# Sensors.net
KiCad netlist of a schematic drawn in Altium Designer
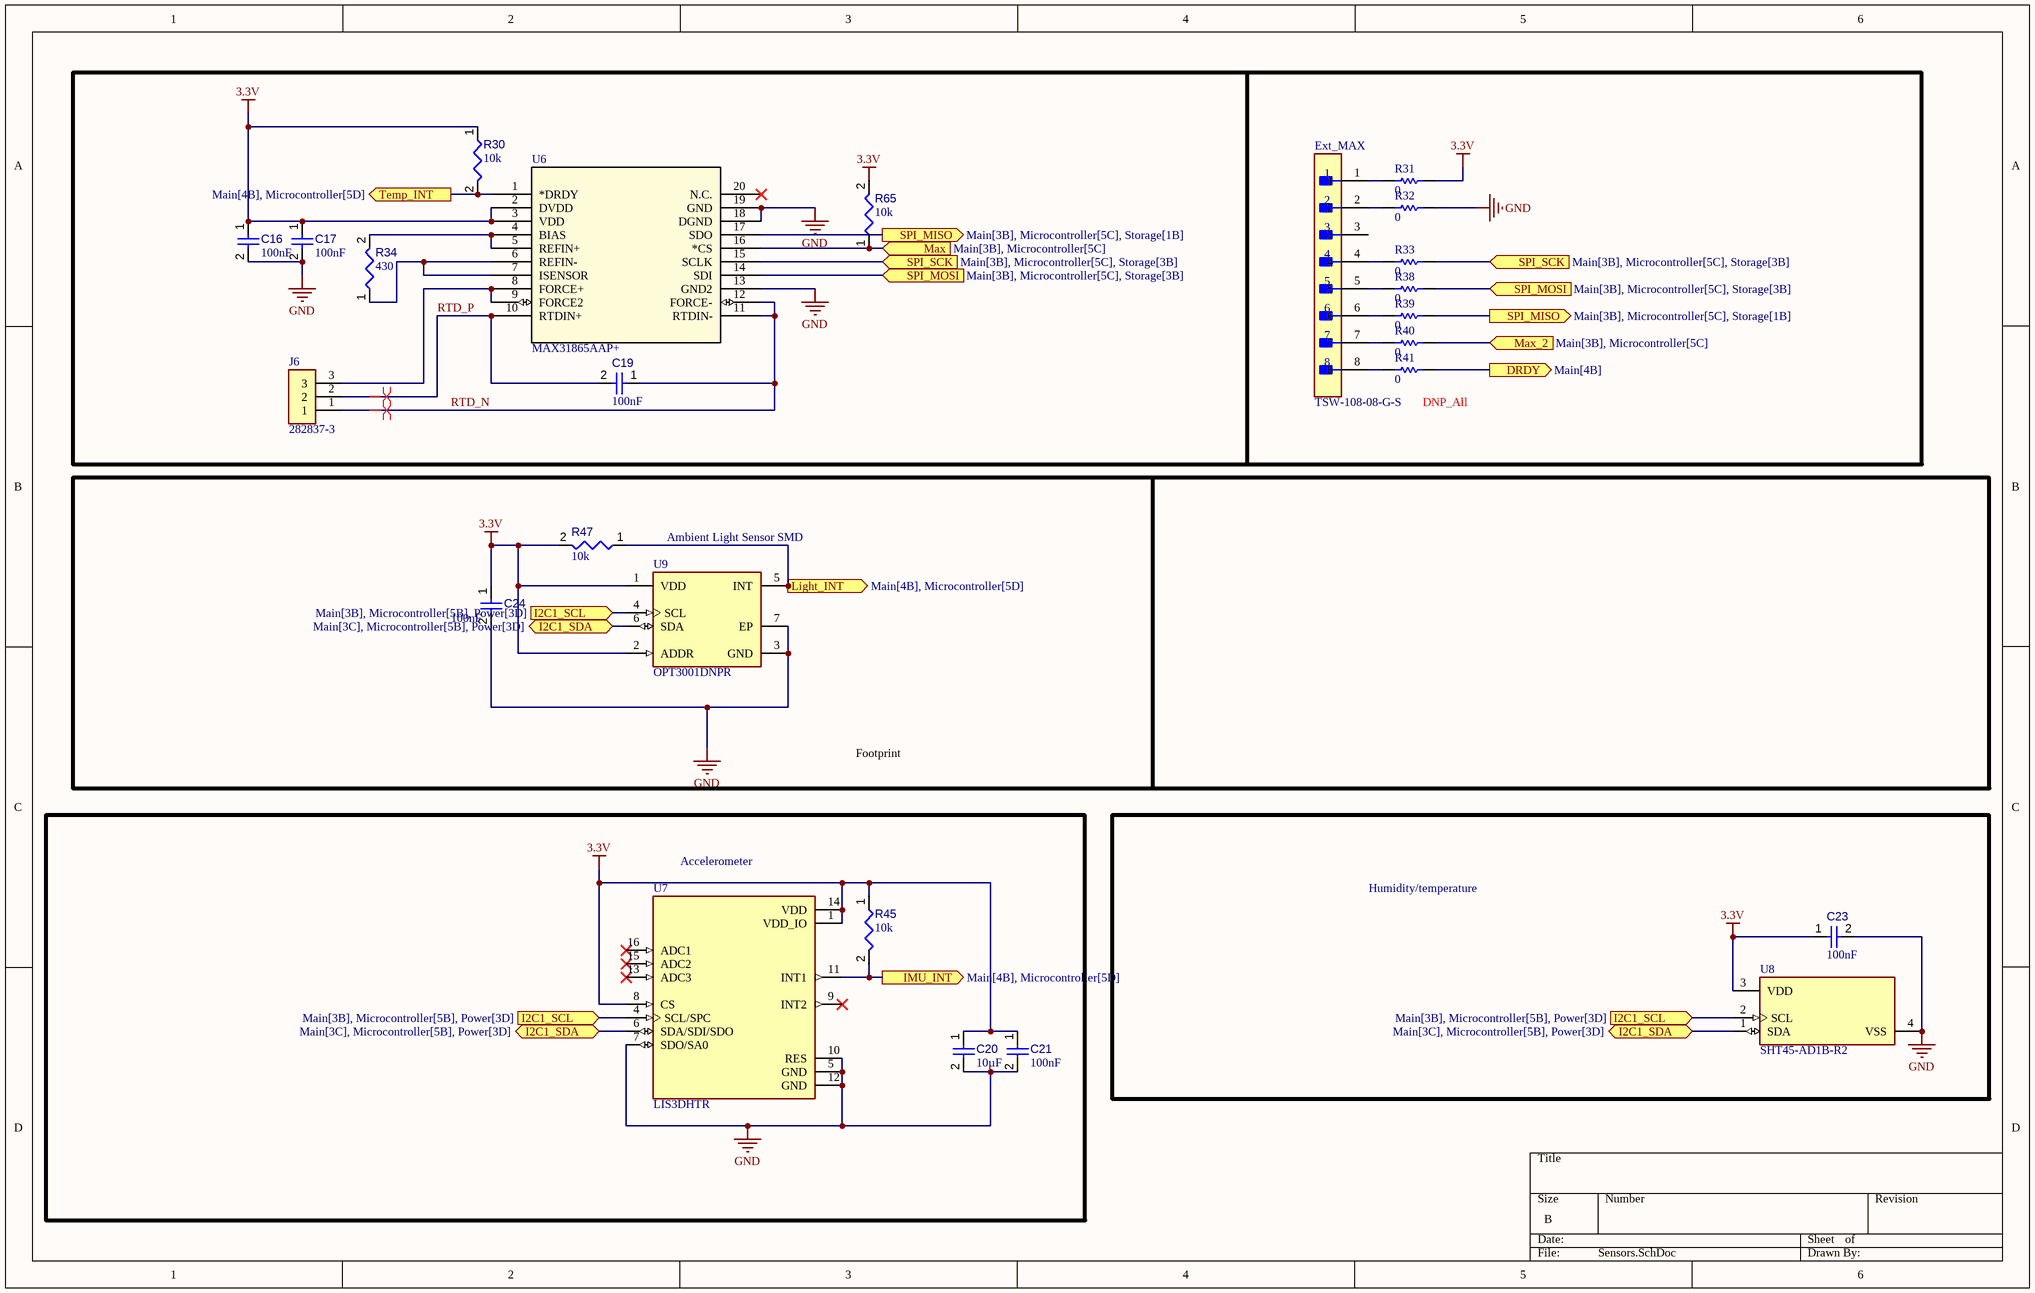
[diagram p0: Sensors.SchDoc]

(export (version "E")
  (design (tool "Eeschema 10.0.6"))
  (components
    (comp (ref "C16")
      (value "100nF")
      (footprint "FP-GCJ188-0_2-IPC_C")
      (description "16V 100nF X7R ±10% 0603 Multilayer Ceramic Capacitors MLCC - SMD/SMT ROHS")
      (fields (field (name "TOLERANCE") "10%") (field (name "Comment") "GCJ188R71C104KA01D"))
      (libsource (lib "Buddhi Rashmika") (part "CAP-NP-2"))
    )
    (comp (ref "C17")
      (value "100nF")
      (footprint "FP-GCJ188-0_2-IPC_C")
      (description "16V 100nF X7R ±10% 0603 Multilayer Ceramic Capacitors MLCC - SMD/SMT ROHS")
      (fields (field (name "TOLERANCE") "10%") (field (name "Comment") "GCJ188R71C104KA01D"))
      (libsource (lib "Buddhi Rashmika") (part "CAP-NP-2"))
    )
    (comp (ref "C19")
      (value "100nF")
      (footprint "FP-GCJ188-0_2-IPC_C")
      (description "16V 100nF X7R ±10% 0603 Multilayer Ceramic Capacitors MLCC - SMD/SMT ROHS")
      (fields (field (name "TOLERANCE") "10%") (field (name "Comment") "GCJ188R71C104KA01D"))
      (libsource (lib "Buddhi Rashmika") (part "CAP-NP-2"))
    )
    (comp (ref "C20")
      (value "10µF")
      (footprint "CAPC3216X180X50NL20T25")
      (description "Chip Capacitor, 10 uF, +/- 10%, 16 V, 1206 (3216 Metric)")
      (fields (field (name "TOLERANCE") "10%") (field (name "Comment") "Capacitor 10 uF +/- 10% 16 V 1206"))
      (libsource (lib "Buddhi Rashmika") (part "CAP-NP-2"))
    )
    (comp (ref "C21")
      (value "100nF")
      (footprint "FP-GCJ188-0_2-IPC_C")
      (description "16V 100nF X7R ±10% 0603 Multilayer Ceramic Capacitors MLCC - SMD/SMT ROHS")
      (fields (field (name "TOLERANCE") "10%") (field (name "Comment") "GCJ188R71C104KA01D"))
      (libsource (lib "Buddhi Rashmika") (part "CAP-NP-2"))
    )
    (comp (ref "C23")
      (value "100nF")
      (footprint "FP-GCJ188-0_2-IPC_C")
      (description "16V 100nF X7R ±10% 0603 Multilayer Ceramic Capacitors MLCC - SMD/SMT ROHS")
      (fields (field (name "TOLERANCE") "10%") (field (name "Comment") "GCJ188R71C104KA01D"))
      (libsource (lib "Buddhi Rashmika") (part "CAP-NP-2"))
    )
    (comp (ref "C24")
      (value "100nF")
      (footprint "FP-GCJ188-0_2-IPC_C")
      (description "16V 100nF X7R ±10% 0603 Multilayer Ceramic Capacitors MLCC - SMD/SMT ROHS")
      (fields (field (name "TOLERANCE") "10%") (field (name "Comment") "GCJ188R71C104KA01D"))
      (libsource (lib "Buddhi Rashmika") (part "CAP-NP-2"))
    )
    (comp (ref "Ext_MAX")
      (value "TSW-108-08-G-S")
      (footprint "FP-TSW-108-08-G-S-MFG")
      (description "CONN HEADER VERT 8POS 2.54MM")
      (fields
        (field (name "MANUFACTURER") "Samtec")
        (field (name "OCTOPART") "https://octopart.com/tsw-108-08-g-s-samtec-272653")
      )
      (libsource (lib "Altium Content Vault") (part "99ec2b232beb5d2356d4d77f6a047f0"))
    )
    (comp (ref "J6")
      (value "282837-3")
      (footprint "TE_282837-3")
      (description "TERMI-BLOK PCB MOUNT 3P")
      (libsource (lib "Buddhi Rashmika") (part "282837-3"))
    )
    (comp (ref "R30")
      (value "10k")
      (footprint "RESC3216X60X45ML15T20")
      (description "Chip Resistor, 10 KOhm, +/- 1%, 0.25 W, -55 to 155 degC, 1206 (3216 Metric)")
      (fields (field (name "TOLERANCE") "1%") (field (name "POWER") "250mW"))
      (libsource (lib "Buddhi Rashmika") (part "RES-2"))
    )
    (comp (ref "R31")
      (value "0")
      (footprint "RESC2013X60X35ML10T20")
      (description "Chip Resistor, 0 Ohm, 0.125 W, -55 to 155 degC, 0805 (2012 Metric)")
      (fields (field (name "POWER") "125mW") (field (name "TOLERANCE") "5%"))
      (libsource (lib "") (part "RES-2_1"))
    )
    (comp (ref "R32")
      (value "0")
      (footprint "RESC2013X60X35ML10T20")
      (description "Chip Resistor, 0 Ohm, 0.125 W, -55 to 155 degC, 0805 (2012 Metric)")
      (fields (field (name "POWER") "125mW") (field (name "TOLERANCE") "5%"))
      (libsource (lib "") (part "RES-2_1"))
    )
    (comp (ref "R33")
      (value "0")
      (footprint "RESC2013X60X35ML10T20")
      (description "Chip Resistor, 0 Ohm, 0.125 W, -55 to 155 degC, 0805 (2012 Metric)")
      (fields (field (name "POWER") "125mW") (field (name "TOLERANCE") "5%"))
      (libsource (lib "") (part "RES-2_1"))
    )
    (comp (ref "R34")
      (value "430")
      (footprint "FP-RT0805-MFG")
      (description "125mW Thin Film Resistor ±25ppm/℃ ±0.1% 430Ω 0805 Chip Resistor - Surface Mount ROHS")
      (fields (field (name "TOLERANCE") "0.1%") (field (name "Comment") "RT0805BRD07430RL"))
      (libsource (lib "Buddhi Rashmika") (part "RES-2"))
    )
    (comp (ref "R38")
      (value "0")
      (footprint "RESC2013X60X35ML10T20")
      (description "Chip Resistor, 0 Ohm, 0.125 W, -55 to 155 degC, 0805 (2012 Metric)")
      (fields (field (name "POWER") "125mW") (field (name "TOLERANCE") "5%"))
      (libsource (lib "") (part "RES-2_1"))
    )
    (comp (ref "R39")
      (value "0")
      (footprint "RESC2013X60X35ML10T20")
      (description "Chip Resistor, 0 Ohm, 0.125 W, -55 to 155 degC, 0805 (2012 Metric)")
      (fields (field (name "POWER") "125mW") (field (name "TOLERANCE") "5%"))
      (libsource (lib "") (part "RES-2_1"))
    )
    (comp (ref "R40")
      (value "0")
      (footprint "RESC2013X60X35ML10T20")
      (description "Chip Resistor, 0 Ohm, 0.125 W, -55 to 155 degC, 0805 (2012 Metric)")
      (fields (field (name "POWER") "125mW") (field (name "TOLERANCE") "5%"))
      (libsource (lib "") (part "RES-2_1"))
    )
    (comp (ref "R41")
      (value "0")
      (footprint "RESC2013X60X35ML10T20")
      (description "Chip Resistor, 0 Ohm, 0.125 W, -55 to 155 degC, 0805 (2012 Metric)")
      (fields (field (name "POWER") "125mW") (field (name "TOLERANCE") "5%"))
      (libsource (lib "") (part "RES-2_1"))
    )
    (comp (ref "R45")
      (value "10k")
      (footprint "RESC3216X60X45ML15T20")
      (description "Chip Resistor, 10 KOhm, +/- 1%, 0.25 W, -55 to 155 degC, 1206 (3216 Metric)")
      (fields (field (name "TOLERANCE") "1%") (field (name "POWER") "250mW"))
      (libsource (lib "Buddhi Rashmika") (part "RES-2"))
    )
    (comp (ref "R47")
      (value "10k")
      (footprint "RESC3216X60X45ML15T20")
      (description "Chip Resistor, 10 KOhm, +/- 1%, 0.25 W, -55 to 155 degC, 1206 (3216 Metric)")
      (fields (field (name "TOLERANCE") "1%") (field (name "POWER") "250mW"))
      (libsource (lib "Buddhi Rashmika") (part "RES-2"))
    )
    (comp (ref "R65")
      (value "10k")
      (footprint "RESC2013X50X35ML15T15")
      (description "Chip Resistor, 10 KOhm, +/- 1%, 125 mW, -55 to 155 degC, 0805 (2012 Metric)")
      (fields (field (name "TOLERANCE") "1%") (field (name "POWER") "125mW"))
      (libsource (lib "Buddhi Rashmika") (part "RES-2"))
    )
    (comp (ref "U6")
      (value "MAX31865AAP+")
      (footprint "SOP65P777X199-20N")
      (description "RTD-to-Digital Converter")
      (fields (field (name "COPYRIGHT") "Copyright (C) 2025 Ultra Librarian. All rights reserved."))
      (libsource (lib "MAX31865AAP&plus_") (part "MAX31865AAP+"))
    )
    (comp (ref "U7")
      (value "LIS3DHTR")
      (footprint "XDCR_LIS3DHTR")
      (description "Accelerometer X, Y, Z Axis Â±2g, 4g, 8g, 16g 0.5Hz ~ 625Hz 16-LGA (3x3)")
      (fields (field (name "MF") "STMicroelectronics") (field (name "DIGI-KEY_PART_NUMBER") "497-10613-1-ND"))
      (libsource (lib "Buddhi Rashmika") (part "LIS3DHTR"))
    )
    (comp (ref "U8")
      (value "SHT45-AD1B-R2")
      (footprint "FP-SHT45-AD1B-R2-MFG")
      (description "Humidity And Temperature Sensor, Digital, CMOS, 4 Pin, Plastic/epoxy")
      (libsource (lib "Buddhi Rashmika") (part "c94db72837bc77e1548fc45e30bc2b4"))
    )
    (comp (ref "U9")
      (value "OPT3001DNPR")
      (footprint "FP-DNP0006A-MFG")
      (description "SENSOR OPT 550NM AMBIENT 6USON")
      (fields
        (field (name "OCTOPART") "https://octopart.com/opt3001dnpr-texas+instruments-47324050")
        (field (name "MANUFACTURER") "Texas Instruments")
      )
      (libsource (lib "Altium Content Vault") (part "6d36863dc75c3adee7e1b5a0d97a822"))
    )
  )
  (nets
    (net (code "1") (name "/DRDY") (class "Default")
      (node (ref "R41") (pin "2") (pinfunction "2_2") (pintype "passive"))
    )
    (net (code "2") (name "/I2C1_SCL") (class "Default")
      (node (ref "U7") (pin "4") (pinfunction "SCL/SPC_4") (pintype "input"))
      (node (ref "U8") (pin "2") (pinfunction "SCL_2") (pintype "input"))
      (node (ref "U9") (pin "4") (pinfunction "SCL_4") (pintype "input"))
    )
    (net (code "3") (name "/I2C1_SDA") (class "Default")
      (node (ref "U7") (pin "6") (pinfunction "SDA/SDI/SDO_6") (pintype "bidirectional"))
      (node (ref "U8") (pin "1") (pinfunction "SDA_1") (pintype "bidirectional"))
      (node (ref "U9") (pin "6") (pinfunction "SDA_6") (pintype "bidirectional"))
    )
    (net (code "4") (name "/IMU_INT") (class "Default")
      (node (ref "R45") (pin "2") (pinfunction "2_2") (pintype "passive"))
      (node (ref "U7") (pin "11") (pinfunction "INT1_11") (pintype "output"))
    )
    (net (code "5") (name "/Light_INT") (class "Default")
      (node (ref "R47") (pin "1") (pinfunction "1_1") (pintype "passive"))
      (node (ref "U9") (pin "5") (pinfunction "INT_5") (pintype "open_collector"))
    )
    (net (code "6") (name "/Max") (class "Default")
      (node (ref "R65") (pin "1") (pinfunction "1_1") (pintype "passive"))
      (node (ref "U6") (pin "16") (pinfunction "*CS_16") (pintype "passive"))
    )
    (net (code "7") (name "/Max_2") (class "Default")
      (node (ref "R40") (pin "2") (pinfunction "2_2") (pintype "passive"))
    )
    (net (code "8") (name "/RTD_N") (class "Default")
      (node (ref "C19") (pin "1") (pinfunction "1_1") (pintype "passive"))
      (node (ref "J6") (pin "1") (pinfunction "1_1") (pintype "passive"))
      (node (ref "U6") (pin "11") (pinfunction "RTDIN-_11") (pintype "passive"))
      (node (ref "U6") (pin "12") (pinfunction "FORCE-_12") (pintype "bidirectional"))
    )
    (net (code "9") (name "/RTD_P") (class "Default")
      (node (ref "C19") (pin "2") (pinfunction "2_2") (pintype "passive"))
      (node (ref "J6") (pin "2") (pinfunction "2_2") (pintype "passive"))
      (node (ref "U6") (pin "10") (pinfunction "RTDIN+_10") (pintype "passive"))
    )
    (net (code "10") (name "/SPI_MISO") (class "Default")
      (node (ref "R39") (pin "2") (pinfunction "2_2") (pintype "passive"))
      (node (ref "U6") (pin "17") (pinfunction "SDO_17") (pintype "passive"))
    )
    (net (code "11") (name "/SPI_MOSI") (class "Default")
      (node (ref "R38") (pin "2") (pinfunction "2_2") (pintype "passive"))
      (node (ref "U6") (pin "14") (pinfunction "SDI_14") (pintype "passive"))
    )
    (net (code "12") (name "/SPI_SCK") (class "Default")
      (node (ref "R33") (pin "2") (pinfunction "2_2") (pintype "passive"))
      (node (ref "U6") (pin "15") (pinfunction "SCLK_15") (pintype "passive"))
    )
    (net (code "13") (name "/Temp_INT") (class "Default")
      (node (ref "R30") (pin "2") (pinfunction "2_2") (pintype "passive"))
      (node (ref "U6") (pin "1") (pinfunction "*DRDY_1") (pintype "passive"))
    )
    (net (code "14") (name "3.3V") (class "Default")
      (node (ref "C16") (pin "1") (pinfunction "1_1") (pintype "passive"))
      (node (ref "C17") (pin "1") (pinfunction "1_1") (pintype "passive"))
      (node (ref "C20") (pin "1") (pinfunction "1_1") (pintype "passive"))
      (node (ref "C21") (pin "1") (pinfunction "1_1") (pintype "passive"))
      (node (ref "C23") (pin "1") (pinfunction "1_1") (pintype "passive"))
      (node (ref "C24") (pin "1") (pinfunction "1_1") (pintype "passive"))
      (node (ref "R30") (pin "1") (pinfunction "1_1") (pintype "passive"))
      (node (ref "R31") (pin "2") (pinfunction "2_2") (pintype "passive"))
      (node (ref "R45") (pin "1") (pinfunction "1_1") (pintype "passive"))
      (node (ref "R47") (pin "2") (pinfunction "2_2") (pintype "passive"))
      (node (ref "R65") (pin "2") (pinfunction "2_2") (pintype "passive"))
      (node (ref "U6") (pin "2") (pinfunction "DVDD_2") (pintype "power_in"))
      (node (ref "U6") (pin "3") (pinfunction "VDD_3") (pintype "power_in"))
      (node (ref "U7") (pin "1") (pinfunction "VDD_IO_1") (pintype "power_in"))
      (node (ref "U7") (pin "14") (pinfunction "VDD_14") (pintype "power_in"))
      (node (ref "U7") (pin "8") (pinfunction "CS_8") (pintype "input"))
      (node (ref "U8") (pin "3") (pinfunction "VDD_3") (pintype "power_in"))
      (node (ref "U9") (pin "1") (pinfunction "VDD_1") (pintype "power_in"))
      (node (ref "U9") (pin "2") (pinfunction "ADDR_2") (pintype "input"))
    )
    (net (code "15") (name "GND") (class "Default")
      (node (ref "C16") (pin "2") (pinfunction "2_2") (pintype "passive"))
      (node (ref "C17") (pin "2") (pinfunction "2_2") (pintype "passive"))
      (node (ref "C20") (pin "2") (pinfunction "2_2") (pintype "passive"))
      (node (ref "C21") (pin "2") (pinfunction "2_2") (pintype "passive"))
      (node (ref "C23") (pin "2") (pinfunction "2_2") (pintype "passive"))
      (node (ref "C24") (pin "2") (pinfunction "2_2") (pintype "passive"))
      (node (ref "R32") (pin "2") (pinfunction "2_2") (pintype "passive"))
      (node (ref "U6") (pin "13") (pinfunction "GND2_13") (pintype "power_in"))
      (node (ref "U6") (pin "18") (pinfunction "DGND_18") (pintype "power_in"))
      (node (ref "U6") (pin "19") (pinfunction "GND_19") (pintype "power_in"))
      (node (ref "U7") (pin "10") (pinfunction "RES_10") (pintype "passive"))
      (node (ref "U7") (pin "12") (pinfunction "GND_12") (pintype "power_in"))
      (node (ref "U7") (pin "5") (pinfunction "GND_5") (pintype "power_in"))
      (node (ref "U7") (pin "7") (pinfunction "SDO/SA0_7") (pintype "bidirectional"))
      (node (ref "U8") (pin "4") (pinfunction "VSS_4") (pintype "power_in"))
      (node (ref "U9") (pin "3") (pinfunction "GND_3") (pintype "power_in"))
      (node (ref "U9") (pin "7") (pinfunction "EP_7") (pintype "power_in"))
    )
    (net (code "16") (name "Net-(Ext_MAX-Pad1)") (class "Default")
      (node (ref "Ext_MAX") (pin "1") (pinfunction "1_1") (pintype "passive"))
      (node (ref "R31") (pin "1") (pinfunction "1_1") (pintype "passive"))
    )
    (net (code "17") (name "Net-(Ext_MAX-Pad2)") (class "Default")
      (node (ref "Ext_MAX") (pin "2") (pinfunction "2_2") (pintype "passive"))
      (node (ref "R32") (pin "1") (pinfunction "1_1") (pintype "passive"))
    )
    (net (code "18") (name "Net-(Ext_MAX-Pad4)") (class "Default")
      (node (ref "Ext_MAX") (pin "4") (pinfunction "4_4") (pintype "passive"))
      (node (ref "R33") (pin "1") (pinfunction "1_1") (pintype "passive"))
    )
    (net (code "19") (name "Net-(Ext_MAX-Pad5)") (class "Default")
      (node (ref "Ext_MAX") (pin "5") (pinfunction "5_5") (pintype "passive"))
      (node (ref "R38") (pin "1") (pinfunction "1_1") (pintype "passive"))
    )
    (net (code "20") (name "Net-(Ext_MAX-Pad6)") (class "Default")
      (node (ref "Ext_MAX") (pin "6") (pinfunction "6_6") (pintype "passive"))
      (node (ref "R39") (pin "1") (pinfunction "1_1") (pintype "passive"))
    )
    (net (code "21") (name "Net-(Ext_MAX-Pad7)") (class "Default")
      (node (ref "Ext_MAX") (pin "7") (pinfunction "7_7") (pintype "passive"))
      (node (ref "R40") (pin "1") (pinfunction "1_1") (pintype "passive"))
    )
    (net (code "22") (name "Net-(Ext_MAX-Pad8)") (class "Default")
      (node (ref "Ext_MAX") (pin "8") (pinfunction "8_8") (pintype "passive"))
      (node (ref "R41") (pin "1") (pinfunction "1_1") (pintype "passive"))
    )
    (net (code "23") (name "Net-(U6-BIAS)") (class "Default")
      (node (ref "R34") (pin "2") (pinfunction "2_2") (pintype "passive"))
      (node (ref "U6") (pin "4") (pinfunction "BIAS_4") (pintype "passive"))
      (node (ref "U6") (pin "5") (pinfunction "REFIN+_5") (pintype "passive"))
    )
    (net (code "24") (name "Net-(U6-FORCE+)") (class "Default")
      (node (ref "J6") (pin "3") (pinfunction "3_3") (pintype "passive"))
      (node (ref "U6") (pin "8") (pinfunction "FORCE+_8") (pintype "passive"))
      (node (ref "U6") (pin "9") (pinfunction "FORCE2_9") (pintype "bidirectional"))
    )
    (net (code "25") (name "Net-(U6-ISENSOR)") (class "Default")
      (node (ref "R34") (pin "1") (pinfunction "1_1") (pintype "passive"))
      (node (ref "U6") (pin "6") (pinfunction "REFIN-_6") (pintype "passive"))
      (node (ref "U6") (pin "7") (pinfunction "ISENSOR_7") (pintype "passive"))
    )
    (net (code "26") (name "unconnected-(Ext_MAX-Pad3)") (class "Default")
      (node (ref "Ext_MAX") (pin "3") (pinfunction "3_3") (pintype "passive"))
    )
    (net (code "27") (name "unconnected-(U6-N.C.-Pad20)") (class "Default")
      (node (ref "U6") (pin "20") (pinfunction "N.C._20") (pintype "passive+no_connect"))
    )
    (net (code "28") (name "unconnected-(U7-ADC1-Pad16)") (class "Default")
      (node (ref "U7") (pin "16") (pinfunction "ADC1_16") (pintype "input+no_connect"))
    )
    (net (code "29") (name "unconnected-(U7-ADC2-Pad15)") (class "Default")
      (node (ref "U7") (pin "15") (pinfunction "ADC2_15") (pintype "input+no_connect"))
    )
    (net (code "30") (name "unconnected-(U7-ADC3-Pad13)") (class "Default")
      (node (ref "U7") (pin "13") (pinfunction "ADC3_13") (pintype "input+no_connect"))
    )
    (net (code "31") (name "unconnected-(U7-INT2-Pad9)") (class "Default")
      (node (ref "U7") (pin "9") (pinfunction "INT2_9") (pintype "output+no_connect"))
    )
  )
)
